# Shema.net
KiCad netlist of a schematic drawn in Altium Designer
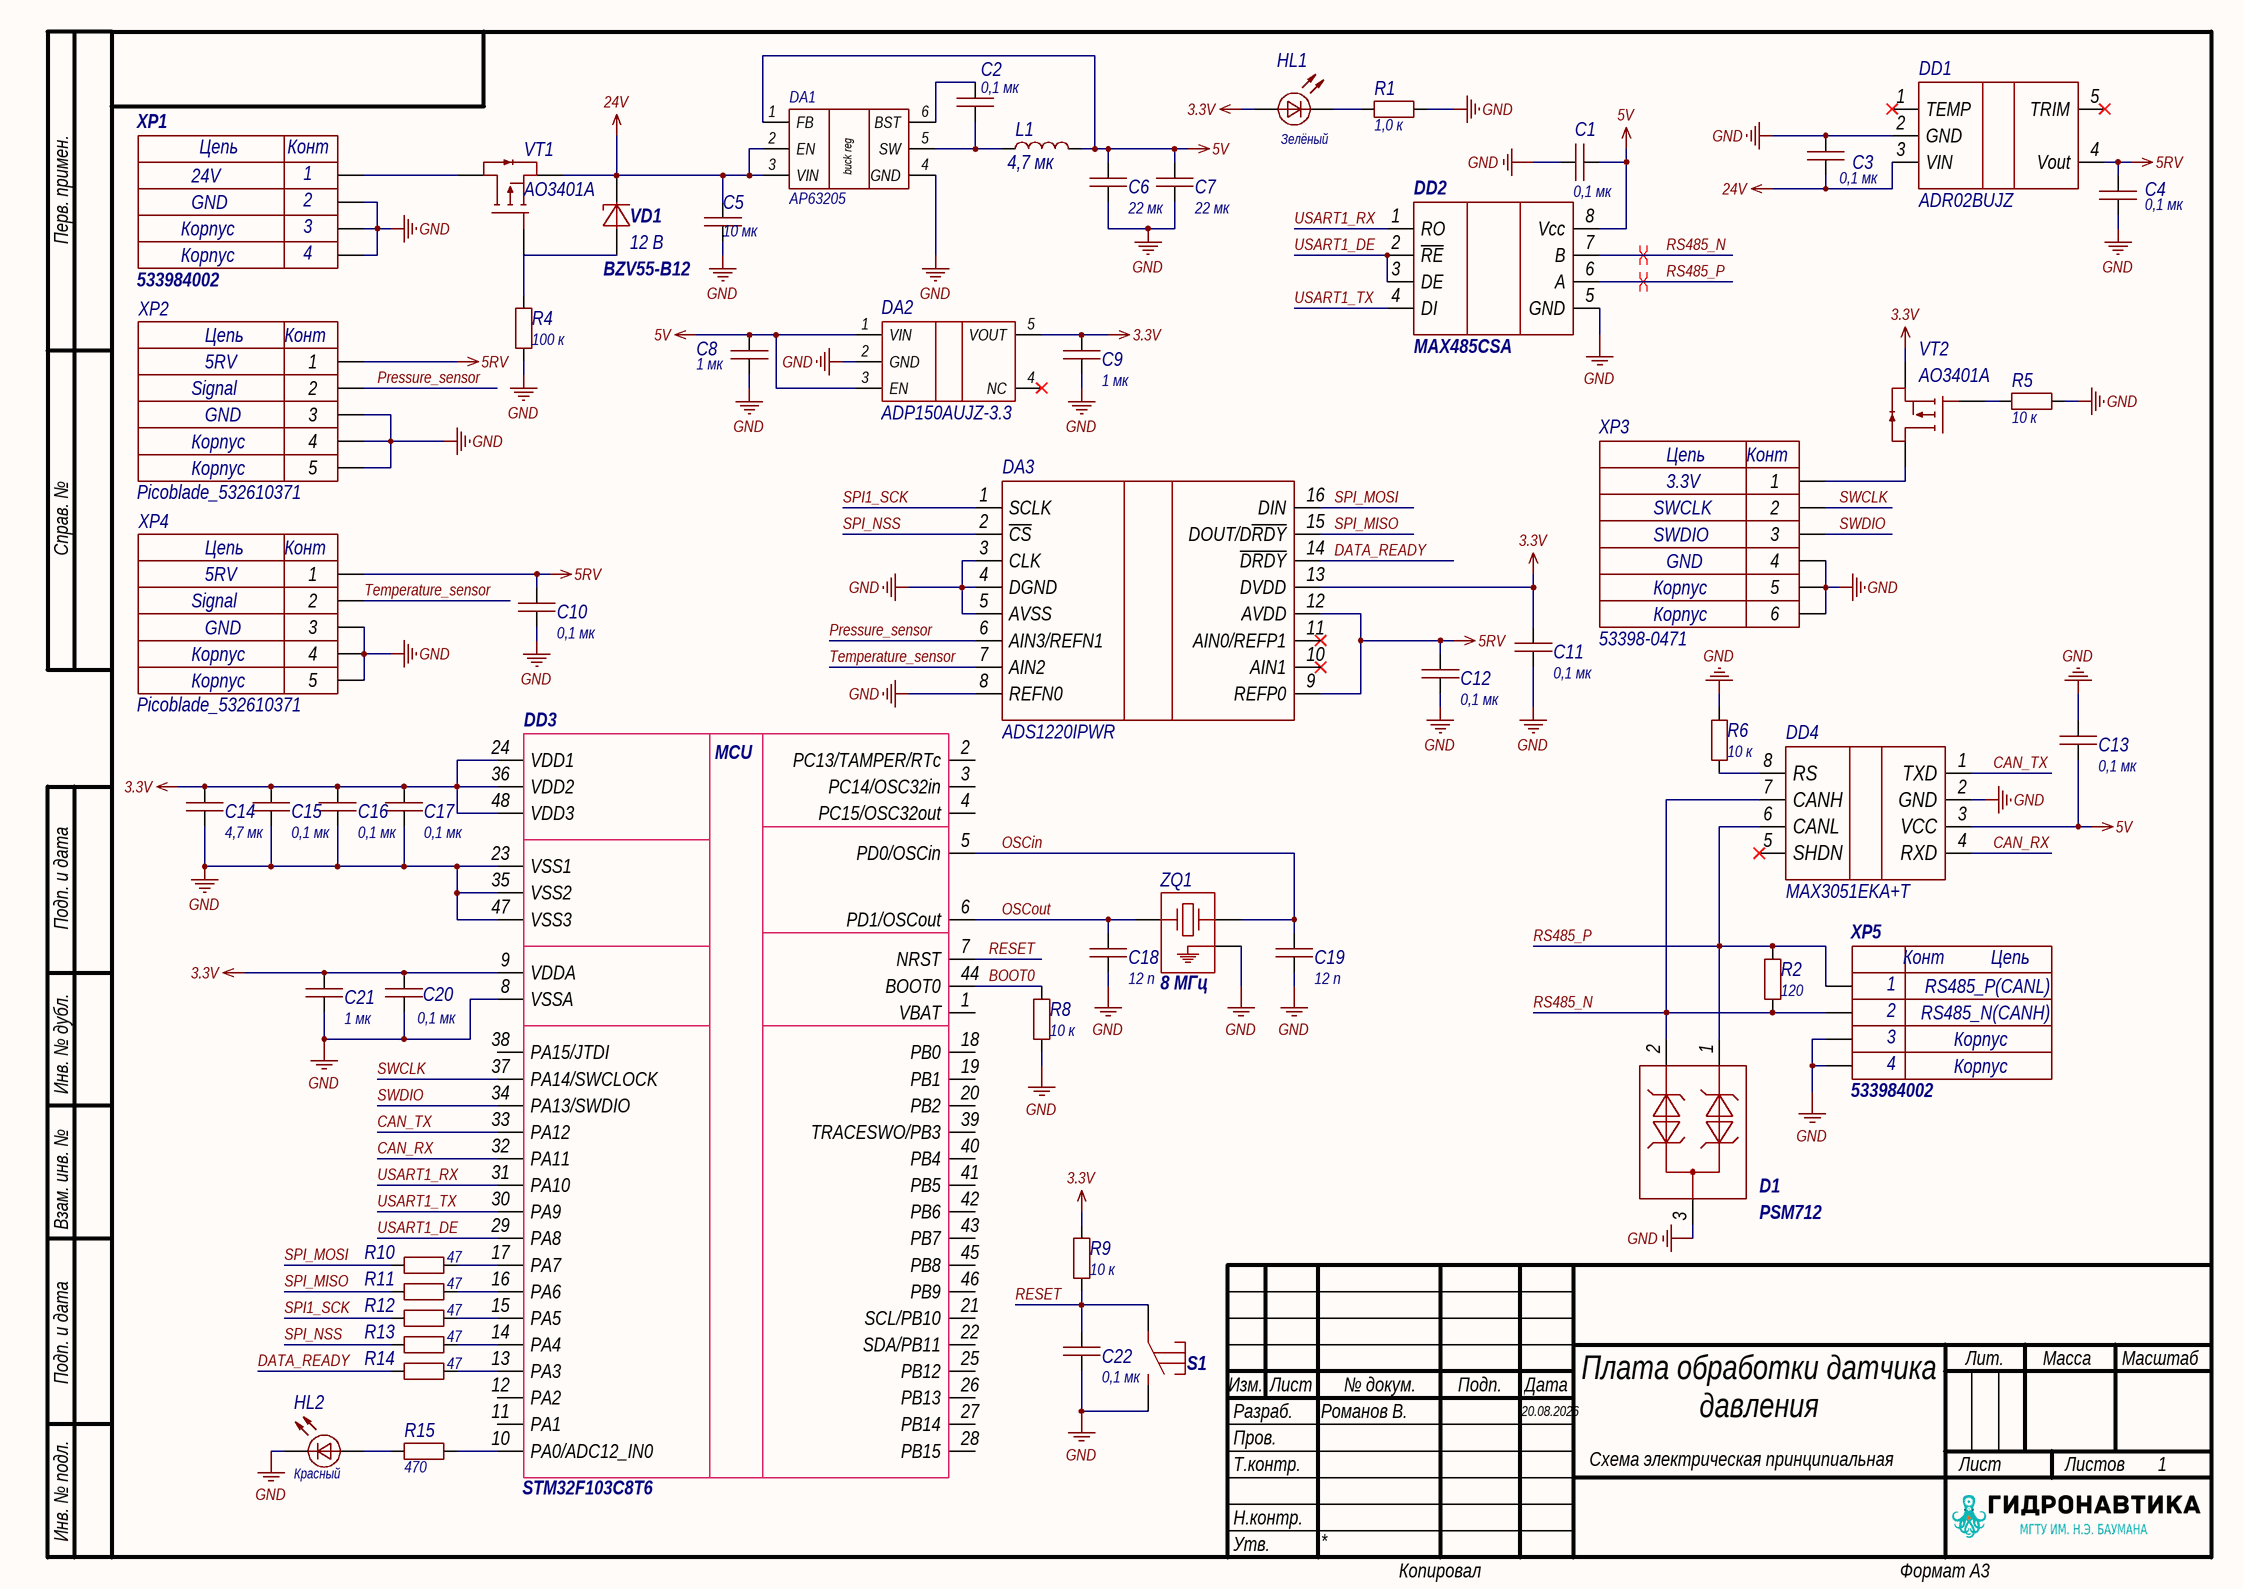
[diagram p0: Shema.SchDoc]

(export (version "E")
  (design (tool "Eeschema 10.0.6"))
  (components
    (comp (ref "C1")
      (value "0,1 мк")
      (footprint "0603C")
      (description "Конденсатор 0603C ёмкостью 0,1 мк 10%, 50 В, X7R")
      (fields (field (name "PART NUMBER") "Capacitor_0,1u_10_50V_X7R_0603C") (field (name "TOLERANCE") "10%"))
      (libsource (lib "Hydrolib") (part "Capacitor"))
    )
    (comp (ref "C2")
      (value "0,1 мк")
      (footprint "0603C")
      (description "Конденсатор 0603C ёмкостью 0,1 мк 10%, 50 В, X7R")
      (fields (field (name "PART NUMBER") "Capacitor_0,1u_10_50V_X7R_0603C") (field (name "TOLERANCE") "10%"))
      (libsource (lib "Hydrolib") (part "Capacitor"))
    )
    (comp (ref "C3")
      (value "0,1 мк")
      (footprint "0603C")
      (description "Конденсатор 0603C ёмкостью 0,1 мк 10%, 50 В, X7R")
      (fields (field (name "PART NUMBER") "Capacitor_0,1u_10_50V_X7R_0603C") (field (name "TOLERANCE") "10%"))
      (libsource (lib "Hydrolib") (part "Capacitor"))
    )
    (comp (ref "C4")
      (value "0,1 мк")
      (footprint "0603C")
      (description "Конденсатор 0603C ёмкостью 0,1 мк 10%, 50 В, X7R")
      (fields (field (name "PART NUMBER") "Capacitor_0,1u_10_50V_X7R_0603C") (field (name "TOLERANCE") "10%"))
      (libsource (lib "Hydrolib") (part "Capacitor"))
    )
    (comp (ref "C5")
      (value "10 мк")
      (footprint "1210C")
      (description "Конденсатор 1210C ёмкостью 10 мк 10%, 35 В, X7R")
      (fields (field (name "PART NUMBER") "Capacitor_10u_10_35V_X7R_1210C") (field (name "TOLERANCE") "10%"))
      (libsource (lib "Hydrolib") (part "Capacitor"))
    )
    (comp (ref "C6")
      (value "22 мк")
      (footprint "1210C")
      (description "Конденсатор 1210C ёмкостью 22 мк 10%, 25 В, X7R")
      (fields (field (name "PART NUMBER") "Capacitor_22u_10_25V_X7R_1210C") (field (name "TOLERANCE") "10%"))
      (libsource (lib "Hydrolib") (part "Capacitor"))
    )
    (comp (ref "C7")
      (value "22 мк")
      (footprint "1210C")
      (description "Конденсатор 1210C ёмкостью 22 мк 10%, 25 В, X7R")
      (fields (field (name "PART NUMBER") "Capacitor_22u_10_25V_X7R_1210C") (field (name "TOLERANCE") "10%"))
      (libsource (lib "Hydrolib") (part "Capacitor"))
    )
    (comp (ref "C8")
      (value "1 мк")
      (footprint "0603C")
      (description "Конденсатор 0603C ёмкостью 1 мк 10%, 25 В, X7R")
      (fields (field (name "PART NUMBER") "Capacitor_1u_10_25V_X7R_0603C") (field (name "TOLERANCE") "10%"))
      (libsource (lib "Hydrolib") (part "Capacitor"))
    )
    (comp (ref "C9")
      (value "1 мк")
      (footprint "0603C")
      (description "Конденсатор 0603C ёмкостью 1 мк 10%, 25 В, X7R")
      (fields (field (name "PART NUMBER") "Capacitor_1u_10_25V_X7R_0603C") (field (name "TOLERANCE") "10%"))
      (libsource (lib "Hydrolib") (part "Capacitor"))
    )
    (comp (ref "C10")
      (value "0,1 мк")
      (footprint "0603C")
      (description "Конденсатор 0603C ёмкостью 0,1 мк 10%, 50 В, X7R")
      (fields (field (name "PART NUMBER") "Capacitor_0,1u_10_50V_X7R_0603C") (field (name "TOLERANCE") "10%"))
      (libsource (lib "Hydrolib") (part "Capacitor"))
    )
    (comp (ref "C11")
      (value "0,1 мк")
      (footprint "0603C")
      (description "Конденсатор 0603C ёмкостью 0,1 мк 10%, 50 В, X7R")
      (fields (field (name "PART NUMBER") "Capacitor_0,1u_10_50V_X7R_0603C") (field (name "TOLERANCE") "10%"))
      (libsource (lib "Hydrolib") (part "Capacitor"))
    )
    (comp (ref "C12")
      (value "0,1 мк")
      (footprint "0603C")
      (description "Конденсатор 0603C ёмкостью 0,1 мк 10%, 50 В, X7R")
      (fields (field (name "PART NUMBER") "Capacitor_0,1u_10_50V_X7R_0603C") (field (name "TOLERANCE") "10%"))
      (libsource (lib "Hydrolib") (part "Capacitor"))
    )
    (comp (ref "C13")
      (value "0,1 мк")
      (footprint "0603C")
      (description "Конденсатор 0603C ёмкостью 0,1 мк 10%, 50 В, X7R")
      (fields (field (name "PART NUMBER") "Capacitor_0,1u_10_50V_X7R_0603C") (field (name "TOLERANCE") "10%"))
      (libsource (lib "Hydrolib") (part "Capacitor"))
    )
    (comp (ref "C14")
      (value "4,7 мк")
      (footprint "1206C")
      (description "Конденсатор 1206C ёмкостью 4,7 мк 10%, 50 В, X7R")
      (fields (field (name "PART NUMBER") "Capacitor_4,7u_10_50V_X7R_1206C") (field (name "TOLERANCE") "10%"))
      (libsource (lib "Hydrolib") (part "Capacitor"))
    )
    (comp (ref "C15")
      (value "0,1 мк")
      (footprint "0603C")
      (description "Конденсатор 0603C ёмкостью 0,1 мк 10%, 50 В, X7R")
      (fields (field (name "PART NUMBER") "Capacitor_0,1u_10_50V_X7R_0603C") (field (name "TOLERANCE") "10%"))
      (libsource (lib "Hydrolib") (part "Capacitor"))
    )
    (comp (ref "C16")
      (value "0,1 мк")
      (footprint "0603C")
      (description "Конденсатор 0603C ёмкостью 0,1 мк 10%, 50 В, X7R")
      (fields (field (name "PART NUMBER") "Capacitor_0,1u_10_50V_X7R_0603C") (field (name "TOLERANCE") "10%"))
      (libsource (lib "Hydrolib") (part "Capacitor"))
    )
    (comp (ref "C17")
      (value "0,1 мк")
      (footprint "0603C")
      (description "Конденсатор 0603C ёмкостью 0,1 мк 10%, 50 В, X7R")
      (fields (field (name "PART NUMBER") "Capacitor_0,1u_10_50V_X7R_0603C") (field (name "TOLERANCE") "10%"))
      (libsource (lib "Hydrolib") (part "Capacitor"))
    )
    (comp (ref "C18")
      (value "12 п")
      (footprint "0603C")
      (description "Конденсатор 0603C ёмкостью 12 п 5%, 50 В, NP0")
      (fields
        (field (name "PART NUMBER") "Capacitor_12p_5_50V_NP0_0603C")
        (field (name "TOLERANCE") "5%")
        (field (name "АВТОР") "glebmih")
      )
      (libsource (lib "Hydrolib") (part "Capacitor"))
    )
    (comp (ref "C19")
      (value "12 п")
      (footprint "0603C")
      (description "Конденсатор 0603C ёмкостью 12 п 5%, 50 В, NP0")
      (fields
        (field (name "PART NUMBER") "Capacitor_12p_5_50V_NP0_0603C")
        (field (name "TOLERANCE") "5%")
        (field (name "АВТОР") "glebmih")
      )
      (libsource (lib "Hydrolib") (part "Capacitor"))
    )
    (comp (ref "C20")
      (value "0,1 мк")
      (footprint "0603C")
      (description "Конденсатор 0603C ёмкостью 0,1 мк 10%, 50 В, X7R")
      (fields (field (name "PART NUMBER") "Capacitor_0,1u_10_50V_X7R_0603C") (field (name "TOLERANCE") "10%"))
      (libsource (lib "Hydrolib") (part "Capacitor"))
    )
    (comp (ref "C21")
      (value "1 мк")
      (footprint "0603C")
      (description "Конденсатор 0603C ёмкостью 1 мк 10%, 25 В, X7R")
      (fields (field (name "PART NUMBER") "Capacitor_1u_10_25V_X7R_0603C") (field (name "TOLERANCE") "10%"))
      (libsource (lib "Hydrolib") (part "Capacitor"))
    )
    (comp (ref "C22")
      (value "0,1 мк")
      (footprint "0603C")
      (description "Конденсатор 0603C ёмкостью 0,1 мк 10%, 50 В, X7R")
      (fields (field (name "PART NUMBER") "Capacitor_0,1u_10_50V_X7R_0603C") (field (name "TOLERANCE") "10%"))
      (libsource (lib "Hydrolib") (part "Capacitor"))
    )
    (comp (ref "D1")
      (value "PSM712")
      (footprint "SOT23-3")
      (description "Защитный диод для линии RS-485")
      (libsource (lib "Hydrolib") (part "TVS_2_2dir"))
    )
    (comp (ref "DA1")
      (value "AP63205")
      (footprint "TSOT26")
      (description "DC-DC понижающий преобразователь, Vin: 3.8 - 40 В; 5 В; 2 А")
      (fields (field (name "АВТОР") "glebmih"))
      (libsource (lib "Hydrolib") (part "AP63205"))
    )
    (comp (ref "DA2")
      (value "ADP150AUJZ-3.3")
      (footprint "SOT23-5")
      (description "Стабилизатор напряжения 3.3В 150мА")
      (fields (field (name "АВТОР") "glebmih"))
      (libsource (lib "Hydrolib") (part "ADP150AUJZ-3.3"))
    )
    (comp (ref "DA3")
      (value "ADS1220IPWR")
      (footprint "TSSOP-16")
      (description "24-Бит Sigma-Delta аналого-цифровой преобразователь")
      (fields (field (name "АВТОР") "Vouka06"))
      (libsource (lib "Hydrolib") (part "ADS1220IPWR"))
    )
    (comp (ref "DD1")
      (value "ADR02BUJZ")
      (footprint "SOT23-5")
      (description "Источник опорного напряжения, 5В")
      (fields (field (name "АВТОР") "Vouka05"))
      (libsource (lib "Hydrolib") (part "ADR02BUJZ"))
    )
    (comp (ref "DD2")
      (value "MAX485CSA")
      (footprint "SOIC-8")
      (description "RS-485 приёмопередатчик")
      (libsource (lib "Hydrolib") (part "MAX485CSA"))
    )
    (comp (ref "DD3")
      (value "STM32F103C8T6")
      (footprint "LQFP48")
      (description "Микроконтроллер")
      (fields (field (name "MANUFACTURER") "ST Microelectronics") (field (name "VALUE1") "MCU"))
      (libsource (lib "Hydrolib") (part "STM32F103C8T6"))
    )
    (comp (ref "DD4")
      (value "MAX3051EKA+T")
      (footprint "SOT-23-8")
      (description "CAN трансивер 1Mbps +3.3В")
      (fields (field (name "АВТОР") "Vouka06"))
      (libsource (lib "Hydrolib") (part "MAX3051EKA+T"))
    )
    (comp (ref "HL1")
      (value "Зелёный")
      (footprint "0805D")
      (description "Светодиод")
      (fields (field (name "PART NUMBER") "LED"))
      (libsource (lib "Hydrolib") (part "LED"))
    )
    (comp (ref "HL2")
      (value "Красный")
      (footprint "0805D")
      (description "Светодиод")
      (fields (field (name "PART NUMBER") "LED"))
      (libsource (lib "Hydrolib") (part "LED"))
    )
    (comp (ref "L1")
      (value "4,7 мк")
      (footprint "IHLP-2525")
      (description "ЧИП-индуктивность экранированная 4,7мкГн ±20% 5,5A 40мОм 2525")
      (fields (field (name "PART NUMBER") "IHLP2525CZER4R7M01"))
      (libsource (lib "Hydrolib") (part "Inductance"))
    )
    (comp (ref "R1")
      (value "1,0 к")
      (footprint "0603R")
      (description "Резистор номиналом 1,0 кОм 1%")
      (fields (field (name "PART NUMBER") "Resistor_1.0k_1_0603") (field (name "TOLERANCE") "1%"))
      (libsource (lib "Hydrolib") (part "Resistor"))
    )
    (comp (ref "R2")
      (value "120")
      (footprint "1206R")
      (description "Резистор номиналом 120 Ом 1%")
      (fields
        (field (name "PART NUMBER") "Resistor_120_1_1206")
        (field (name "TOLERANCE") "1%")
        (field (name "АВТОР") "glebmih")
      )
      (libsource (lib "") (part "Resistor_1"))
    )
    (comp (ref "R4")
      (value "100 к")
      (footprint "0603R")
      (description "Резистор номиналом 100 кОм 1%")
      (fields (field (name "PART NUMBER") "Resistor_100k_1_0603") (field (name "TOLERANCE") "1%"))
      (libsource (lib "") (part "Resistor_1"))
    )
    (comp (ref "R5")
      (value "10 к")
      (footprint "0603R")
      (description "Резистор номиналом 10 кОм 1%")
      (fields (field (name "PART NUMBER") "Resistor_10k_1_0603") (field (name "TOLERANCE") "1%"))
      (libsource (lib "Hydrolib") (part "Resistor"))
    )
    (comp (ref "R6")
      (value "10 к")
      (footprint "0603R")
      (description "Резистор номиналом 10 кОм 1%")
      (fields (field (name "PART NUMBER") "Resistor_10k_1_0603") (field (name "TOLERANCE") "1%"))
      (libsource (lib "Hydrolib") (part "Resistor"))
    )
    (comp (ref "R8")
      (value "10 к")
      (footprint "0603R")
      (description "Резистор номиналом 10 кОм 1%")
      (fields (field (name "PART NUMBER") "Resistor_10k_1_0603") (field (name "TOLERANCE") "1%"))
      (libsource (lib "") (part "Resistor_2"))
    )
    (comp (ref "R9")
      (value "10 к")
      (footprint "0603R")
      (description "Резистор номиналом 10 кОм 1%")
      (fields (field (name "PART NUMBER") "Resistor_10k_1_0603") (field (name "TOLERANCE") "1%"))
      (libsource (lib "") (part "Resistor_2"))
    )
    (comp (ref "R10")
      (value "47")
      (footprint "0603R")
      (description "Резистор номиналом 47 Ом 1%")
      (fields (field (name "PART NUMBER") "Resistor_47_1_0603") (field (name "TOLERANCE") "1%"))
      (libsource (lib "Hydrolib") (part "Resistor"))
    )
    (comp (ref "R11")
      (value "47")
      (footprint "0603R")
      (description "Резистор номиналом 47 Ом 1%")
      (fields (field (name "PART NUMBER") "Resistor_47_1_0603") (field (name "TOLERANCE") "1%"))
      (libsource (lib "Hydrolib") (part "Resistor"))
    )
    (comp (ref "R12")
      (value "47")
      (footprint "0603R")
      (description "Резистор номиналом 47 Ом 1%")
      (fields (field (name "PART NUMBER") "Resistor_47_1_0603") (field (name "TOLERANCE") "1%"))
      (libsource (lib "Hydrolib") (part "Resistor"))
    )
    (comp (ref "R13")
      (value "47")
      (footprint "0603R")
      (description "Резистор номиналом 47 Ом 1%")
      (fields (field (name "PART NUMBER") "Resistor_47_1_0603") (field (name "TOLERANCE") "1%"))
      (libsource (lib "Hydrolib") (part "Resistor"))
    )
    (comp (ref "R14")
      (value "47")
      (footprint "0603R")
      (description "Резистор номиналом 47 Ом 1%")
      (fields (field (name "PART NUMBER") "Resistor_47_1_0603") (field (name "TOLERANCE") "1%"))
      (libsource (lib "Hydrolib") (part "Resistor"))
    )
    (comp (ref "R15")
      (value "470")
      (footprint "0603R")
      (description "Резистор номиналом 470 Ом 1%")
      (fields (field (name "PART NUMBER") "Resistor_470_1_0603") (field (name "TOLERANCE") "1%"))
      (libsource (lib "Hydrolib") (part "Resistor"))
    )
    (comp (ref "S1")
      (value "Tact_button")
      (footprint "Button_SMD_10mm")
      (description "Тактовая кнопка")
      (libsource (lib "Hydrolib") (part "Tact_button"))
    )
    (comp (ref "VD1")
      (value "BZV55-B12")
      (footprint "mini_MELF_3.5mm")
      (description "Стабилитрон 12В, 5%, 0.5Вт")
      (fields (field (name "ALTIUM_VALUE") "12 В") (field (name "АВТОР") "rreali"))
      (libsource (lib "Hydrolib") (part "Zener"))
    )
    (comp (ref "VT1")
      (value "AO3401A")
      (footprint "SOT23-3")
      (description "P-канальный MOSFET")
      (libsource (lib "Hydrolib") (part "MOSFET P-channel 2"))
    )
    (comp (ref "VT2")
      (value "AO3401A")
      (footprint "SOT23-3")
      (description "P-канальный MOSFET")
      (libsource (lib "Hydrolib") (part "MOSFET P-channel 2"))
    )
    (comp (ref "XP1")
      (value "533984002")
      (footprint "Picoblade_533984002")
      (description "2pin, 1.25mm, вилка, PicoBlade, на плату, SMT")
      (fields
        (field (name "VALUE3") "Корпус")
        (field (name "VALUE2") "GND")
        (field (name "VALUE4") "Корпус")
        (field (name "VALUE1") "24V")
        (field (name "PART NUMBER") "Picoblade_533984002")
        (field (name "АВТОР") "rreali")
      )
      (libsource (lib "Hydrolib") (part "Conn_2pin_2shield"))
    )
    (comp (ref "XP2")
      (value "Picoblade_532610371")
      (footprint "CONN_532610001-SD_03_MOL")
      (description "Picoblade 3-pin разъем")
      (fields
        (field (name "VALUE5") "Корпус")
        (field (name "VALUE4") "Корпус")
        (field (name "VALUE3") "GND")
        (field (name "VALUE2") "Signal")
        (field (name "VALUE1") "5RV")
        (field (name "АВТОР") "Vouka06")
      )
      (libsource (lib "Hydrolib") (part "Picoblade_532610371"))
    )
    (comp (ref "XP3")
      (value "53398-0471")
      (footprint "53398-0471")
      (description "Разъем PicoBlade 1.25 мм, 4pin")
      (fields
        (field (name "VALUE6") "Корпус")
        (field (name "VALUE5") "Корпус")
        (field (name "VALUE4") "GND")
        (field (name "VALUE3") "SWDIO")
        (field (name "VALUE2") "SWCLK")
        (field (name "VALUE1") "3.3V")
        (field (name "PART NUMBER") "PicoBlade_53398-0471")
        (field (name "АВТОР") "Vouka06")
      )
      (libsource (lib "Hydrolib") (part "PicoBlade_53398-0471"))
    )
    (comp (ref "XP4")
      (value "Picoblade_532610371")
      (footprint "CONN_532610001-SD_03_MOL")
      (description "Picoblade 3-pin разъем")
      (fields
        (field (name "VALUE5") "Корпус")
        (field (name "VALUE4") "Корпус")
        (field (name "VALUE3") "GND")
        (field (name "VALUE2") "Signal")
        (field (name "VALUE1") "5RV")
        (field (name "АВТОР") "Vouka06")
      )
      (libsource (lib "Hydrolib") (part "Picoblade_532610371"))
    )
    (comp (ref "XP5")
      (value "533984002")
      (footprint "Picoblade_533984002")
      (description "2pin, 1.25mm, вилка, PicoBlade, на плату, SMT")
      (fields
        (field (name "VALUE3") "Корпус")
        (field (name "VALUE2") "RS485_N(CANH)")
        (field (name "VALUE4") "Корпус")
        (field (name "VALUE1") "RS485_P(CANL)")
        (field (name "PART NUMBER") "Picoblade_533984002")
        (field (name "АВТОР") "rreali")
      )
      (libsource (lib "Hydrolib") (part "Conn_2pin_2shield"))
    )
    (comp (ref "ZQ1")
      (value "8 МГц")
      (footprint "QSMD3.2x2.5")
      (description "Кварцевый резонатор с входом земли")
      (fields (field (name "PART NUMBER") "XTAL_GND"))
      (libsource (lib "Hydrolib") (part "XTAL_GND"))
    )
  )
  (nets
    (net (code "1") (name "/BOOT0") (class "Default")
      (node (ref "DD3") (pin "44") (pinfunction "BOOT0_44") (pintype "passive"))
      (node (ref "R8") (pin "1") (pinfunction "1_1") (pintype "passive"))
    )
    (net (code "2") (name "/CAN_RX") (class "Default")
      (node (ref "DD3") (pin "32") (pinfunction "PA11_32") (pintype "passive"))
      (node (ref "DD4") (pin "4") (pinfunction "RXD_4") (pintype "passive"))
    )
    (net (code "3") (name "/CAN_TX") (class "Default")
      (node (ref "DD3") (pin "33") (pinfunction "PA12_33") (pintype "passive"))
      (node (ref "DD4") (pin "1") (pinfunction "TXD_1") (pintype "passive"))
    )
    (net (code "4") (name "/DATA_READY") (class "Default")
      (node (ref "DA3") (pin "14") (pinfunction "~{DRDY}_14") (pintype "passive"))
      (node (ref "R14") (pin "1") (pinfunction "1_1") (pintype "passive"))
    )
    (net (code "5") (name "/OSCin") (class "Default")
      (node (ref "C19") (pin "2") (pinfunction "2_2") (pintype "passive"))
      (node (ref "DD3") (pin "5") (pinfunction "PD0/OSCin_5") (pintype "passive"))
      (node (ref "ZQ1") (pin "2") (pinfunction "2_2") (pintype "passive"))
    )
    (net (code "6") (name "/OSCout") (class "Default")
      (node (ref "C18") (pin "2") (pinfunction "2_2") (pintype "passive"))
      (node (ref "DD3") (pin "6") (pinfunction "PD1/OSCout_6") (pintype "passive"))
      (node (ref "ZQ1") (pin "1") (pinfunction "1_1") (pintype "passive"))
    )
    (net (code "7") (name "/Pressure_sensor") (class "Default")
      (node (ref "DA3") (pin "6") (pinfunction "AIN3/REFN1_6") (pintype "passive"))
      (node (ref "XP2") (pin "2") (pinfunction "2_2") (pintype "passive"))
    )
    (net (code "8") (name "/RESET") (class "Default")
      (node (ref "C22") (pin "1") (pinfunction "1_1") (pintype "passive"))
      (node (ref "DD3") (pin "7") (pinfunction "NRST_7") (pintype "passive"))
      (node (ref "R9") (pin "2") (pinfunction "2_2") (pintype "passive"))
      (node (ref "S1") (pin "1") (pinfunction "1_1") (pintype "passive"))
    )
    (net (code "9") (name "/RS485_N") (class "Default")
      (node (ref "D1") (pin "2") (pinfunction "15_2") (pintype "passive"))
      (node (ref "DD2") (pin "7") (pinfunction "B_7") (pintype "passive"))
      (node (ref "DD4") (pin "7") (pinfunction "CANH_7") (pintype "passive"))
      (node (ref "R2") (pin "1") (pinfunction "1_1") (pintype "passive"))
      (node (ref "XP5") (pin "2") (pinfunction "2_2") (pintype "passive"))
    )
    (net (code "10") (name "/RS485_P") (class "Default")
      (node (ref "D1") (pin "1") (pinfunction "14_1") (pintype "passive"))
      (node (ref "DD2") (pin "6") (pinfunction "A_6") (pintype "passive"))
      (node (ref "DD4") (pin "6") (pinfunction "CANL_6") (pintype "passive"))
      (node (ref "R2") (pin "2") (pinfunction "2_2") (pintype "passive"))
      (node (ref "XP5") (pin "1") (pinfunction "1_1") (pintype "passive"))
    )
    (net (code "11") (name "/SPI1_SCK") (class "Default")
      (node (ref "DA3") (pin "1") (pinfunction "SCLK_1") (pintype "passive"))
      (node (ref "R12") (pin "1") (pinfunction "1_1") (pintype "passive"))
    )
    (net (code "12") (name "/SPI_MISO") (class "Default")
      (node (ref "DA3") (pin "15") (pinfunction "DOUT/D~{RDY}_15") (pintype "passive"))
      (node (ref "R11") (pin "1") (pinfunction "1_1") (pintype "passive"))
    )
    (net (code "13") (name "/SPI_MOSI") (class "Default")
      (node (ref "DA3") (pin "16") (pinfunction "DIN_16") (pintype "passive"))
      (node (ref "R10") (pin "1") (pinfunction "1_1") (pintype "passive"))
    )
    (net (code "14") (name "/SPI_NSS") (class "Default")
      (node (ref "DA3") (pin "2") (pinfunction "~{CS}_2") (pintype "passive"))
      (node (ref "R13") (pin "1") (pinfunction "1_1") (pintype "passive"))
    )
    (net (code "15") (name "/SWCLK") (class "Default")
      (node (ref "DD3") (pin "37") (pinfunction "PA14/SWCLOCK_37") (pintype "passive"))
      (node (ref "XP3") (pin "2") (pinfunction "2_2") (pintype "passive"))
    )
    (net (code "16") (name "/SWDIO") (class "Default")
      (node (ref "DD3") (pin "34") (pinfunction "PA13/SWDIO_34") (pintype "passive"))
      (node (ref "XP3") (pin "3") (pinfunction "3_3") (pintype "passive"))
    )
    (net (code "17") (name "/Temperature_sensor") (class "Default")
      (node (ref "DA3") (pin "7") (pinfunction "AIN2_7") (pintype "passive"))
      (node (ref "XP4") (pin "2") (pinfunction "2_2") (pintype "passive"))
    )
    (net (code "18") (name "/USART1_DE") (class "Default")
      (node (ref "DD2") (pin "2") (pinfunction "RE_2") (pintype "passive"))
      (node (ref "DD2") (pin "3") (pinfunction "DE_3") (pintype "passive"))
      (node (ref "DD3") (pin "29") (pinfunction "PA8_29") (pintype "passive"))
    )
    (net (code "19") (name "/USART1_RX") (class "Default")
      (node (ref "DD2") (pin "1") (pinfunction "RO_1") (pintype "passive"))
      (node (ref "DD3") (pin "31") (pinfunction "PA10_31") (pintype "passive"))
    )
    (net (code "20") (name "/USART1_TX") (class "Default")
      (node (ref "DD2") (pin "4") (pinfunction "DI_4") (pintype "passive"))
      (node (ref "DD3") (pin "30") (pinfunction "PA9_30") (pintype "passive"))
    )
    (net (code "21") (name "3.3V") (class "Default")
      (node (ref "C11") (pin "2") (pinfunction "2_2") (pintype "passive"))
      (node (ref "C14") (pin "2") (pinfunction "2_2") (pintype "passive"))
      (node (ref "C15") (pin "2") (pinfunction "2_2") (pintype "passive"))
      (node (ref "C16") (pin "2") (pinfunction "2_2") (pintype "passive"))
      (node (ref "C17") (pin "2") (pinfunction "2_2") (pintype "passive"))
      (node (ref "C20") (pin "2") (pinfunction "2_2") (pintype "passive"))
      (node (ref "C21") (pin "2") (pinfunction "2_2") (pintype "passive"))
      (node (ref "C9") (pin "2") (pinfunction "2_2") (pintype "passive"))
      (node (ref "DA2") (pin "5") (pinfunction "VOUT_5") (pintype "passive"))
      (node (ref "DA3") (pin "13") (pinfunction "DVDD_13") (pintype "passive"))
      (node (ref "DD3") (pin "24") (pinfunction "VDD1_24") (pintype "passive"))
      (node (ref "DD3") (pin "36") (pinfunction "VDD2_36") (pintype "passive"))
      (node (ref "DD3") (pin "48") (pinfunction "VDD3_48") (pintype "passive"))
      (node (ref "DD3") (pin "9") (pinfunction "VDDA_9") (pintype "passive"))
      (node (ref "HL1") (pin "1") (pinfunction "1_1") (pintype "passive"))
      (node (ref "R9") (pin "1") (pinfunction "1_1") (pintype "passive"))
      (node (ref "VT2") (pin "2") (pinfunction "2_2") (pintype "passive"))
    )
    (net (code "22") (name "5RV") (class "Default")
      (node (ref "C10") (pin "2") (pinfunction "2_2") (pintype "passive"))
      (node (ref "C12") (pin "2") (pinfunction "2_2") (pintype "passive"))
      (node (ref "C4") (pin "2") (pinfunction "2_2") (pintype "passive"))
      (node (ref "DA3") (pin "12") (pinfunction "AVDD_12") (pintype "passive"))
      (node (ref "DA3") (pin "9") (pinfunction "REFP0_9") (pintype "passive"))
      (node (ref "DD1") (pin "4") (pinfunction "Vout_4") (pintype "passive"))
      (node (ref "XP2") (pin "1") (pinfunction "1_1") (pintype "passive"))
      (node (ref "XP4") (pin "1") (pinfunction "1_1") (pintype "passive"))
    )
    (net (code "23") (name "5V") (class "Default")
      (node (ref "C1") (pin "2") (pinfunction "2_2") (pintype "passive"))
      (node (ref "C13") (pin "2") (pinfunction "2_2") (pintype "passive"))
      (node (ref "C6") (pin "2") (pinfunction "2_2") (pintype "passive"))
      (node (ref "C7") (pin "2") (pinfunction "2_2") (pintype "passive"))
      (node (ref "C8") (pin "2") (pinfunction "2_2") (pintype "passive"))
      (node (ref "DA1") (pin "1") (pinfunction "FB_1") (pintype "passive"))
      (node (ref "DA2") (pin "1") (pinfunction "VIN_1") (pintype "passive"))
      (node (ref "DA2") (pin "3") (pinfunction "EN_3") (pintype "passive"))
      (node (ref "DD2") (pin "8") (pinfunction "Vcc_8") (pintype "passive"))
      (node (ref "DD4") (pin "3") (pinfunction "VCC_3") (pintype "passive"))
      (node (ref "L1") (pin "2") (pinfunction "2_2") (pintype "passive"))
    )
    (net (code "24") (name "24V") (class "Default")
      (node (ref "C3") (pin "1") (pinfunction "1_1") (pintype "passive"))
      (node (ref "C5") (pin "2") (pinfunction "2_2") (pintype "passive"))
      (node (ref "DA1") (pin "2") (pinfunction "EN_2") (pintype "passive"))
      (node (ref "DA1") (pin "3") (pinfunction "VIN_3") (pintype "passive"))
      (node (ref "DD1") (pin "3") (pinfunction "VIN_3") (pintype "passive"))
      (node (ref "VD1") (pin "2") (pinfunction "2_2") (pintype "passive"))
      (node (ref "VT1") (pin "2") (pinfunction "2_2") (pintype "passive"))
    )
    (net (code "25") (name "GND") (class "Default")
      (node (ref "C1") (pin "1") (pinfunction "1_1") (pintype "passive"))
      (node (ref "C10") (pin "1") (pinfunction "1_1") (pintype "passive"))
      (node (ref "C11") (pin "1") (pinfunction "1_1") (pintype "passive"))
      (node (ref "C12") (pin "1") (pinfunction "1_1") (pintype "passive"))
      (node (ref "C13") (pin "1") (pinfunction "1_1") (pintype "passive"))
      (node (ref "C14") (pin "1") (pinfunction "1_1") (pintype "passive"))
      (node (ref "C15") (pin "1") (pinfunction "1_1") (pintype "passive"))
      (node (ref "C16") (pin "1") (pinfunction "1_1") (pintype "passive"))
      (node (ref "C17") (pin "1") (pinfunction "1_1") (pintype "passive"))
      (node (ref "C18") (pin "1") (pinfunction "1_1") (pintype "passive"))
      (node (ref "C19") (pin "1") (pinfunction "1_1") (pintype "passive"))
      (node (ref "C20") (pin "1") (pinfunction "1_1") (pintype "passive"))
      (node (ref "C21") (pin "1") (pinfunction "1_1") (pintype "passive"))
      (node (ref "C22") (pin "2") (pinfunction "2_2") (pintype "passive"))
      (node (ref "C3") (pin "2") (pinfunction "2_2") (pintype "passive"))
      (node (ref "C4") (pin "1") (pinfunction "1_1") (pintype "passive"))
      (node (ref "C5") (pin "1") (pinfunction "1_1") (pintype "passive"))
      (node (ref "C6") (pin "1") (pinfunction "1_1") (pintype "passive"))
      (node (ref "C7") (pin "1") (pinfunction "1_1") (pintype "passive"))
      (node (ref "C8") (pin "1") (pinfunction "1_1") (pintype "passive"))
      (node (ref "C9") (pin "1") (pinfunction "1_1") (pintype "passive"))
      (node (ref "D1") (pin "3") (pinfunction "16_3") (pintype "passive"))
      (node (ref "DA1") (pin "4") (pinfunction "GND_4") (pintype "passive"))
      (node (ref "DA2") (pin "2") (pinfunction "GND_2") (pintype "passive"))
      (node (ref "DA3") (pin "3") (pinfunction "CLK_3") (pintype "passive"))
      (node (ref "DA3") (pin "4") (pinfunction "DGND_4") (pintype "passive"))
      (node (ref "DA3") (pin "5") (pinfunction "AVSS_5") (pintype "passive"))
      (node (ref "DA3") (pin "8") (pinfunction "REFN0_8") (pintype "passive"))
      (node (ref "DD1") (pin "2") (pinfunction "GND_2") (pintype "passive"))
      (node (ref "DD2") (pin "5") (pinfunction "GND_5") (pintype "passive"))
      (node (ref "DD3") (pin "23") (pinfunction "VSS1_23") (pintype "passive"))
      (node (ref "DD3") (pin "35") (pinfunction "VSS2_35") (pintype "passive"))
      (node (ref "DD3") (pin "47") (pinfunction "VSS3_47") (pintype "passive"))
      (node (ref "DD3") (pin "8") (pinfunction "VSSA_8") (pintype "passive"))
      (node (ref "DD4") (pin "2") (pinfunction "GND_2") (pintype "passive"))
      (node (ref "HL2") (pin "2") (pinfunction "2_2") (pintype "passive"))
      (node (ref "R1") (pin "2") (pinfunction "2_2") (pintype "passive"))
      (node (ref "R4") (pin "1") (pinfunction "1_1") (pintype "passive"))
      (node (ref "R5") (pin "2") (pinfunction "2_2") (pintype "passive"))
      (node (ref "R6") (pin "2") (pinfunction "2_2") (pintype "passive"))
      (node (ref "R8") (pin "2") (pinfunction "2_2") (pintype "passive"))
      (node (ref "S1") (pin "2") (pinfunction "2_2") (pintype "passive"))
      (node (ref "XP1") (pin "2") (pinfunction "2_2") (pintype "passive"))
      (node (ref "XP1") (pin "3") (pinfunction "3_3") (pintype "passive"))
      (node (ref "XP1") (pin "4") (pinfunction "4_4") (pintype "passive"))
      (node (ref "XP2") (pin "3") (pinfunction "3_3") (pintype "passive"))
      (node (ref "XP2") (pin "4") (pinfunction "4_4") (pintype "passive"))
      (node (ref "XP2") (pin "5") (pinfunction "5_5") (pintype "passive"))
      (node (ref "XP3") (pin "4") (pinfunction "4_4") (pintype "passive"))
      (node (ref "XP3") (pin "5") (pinfunction "5_5") (pintype "passive"))
      (node (ref "XP3") (pin "6") (pinfunction "6_6") (pintype "passive"))
      (node (ref "XP4") (pin "3") (pinfunction "3_3") (pintype "passive"))
      (node (ref "XP4") (pin "4") (pinfunction "4_4") (pintype "passive"))
      (node (ref "XP4") (pin "5") (pinfunction "5_5") (pintype "passive"))
      (node (ref "XP5") (pin "3") (pinfunction "3_3") (pintype "passive"))
      (node (ref "XP5") (pin "4") (pinfunction "4_4") (pintype "passive"))
      (node (ref "ZQ1") (pin "3") (pinfunction "3_3") (pintype "passive"))
    )
    (net (code "26") (name "Net-(DA1-BST)") (class "Default")
      (node (ref "C2") (pin "2") (pinfunction "2_2") (pintype "passive"))
      (node (ref "DA1") (pin "6") (pinfunction "BST_6") (pintype "passive"))
    )
    (net (code "27") (name "Net-(DA1-SW)") (class "Default")
      (node (ref "C2") (pin "1") (pinfunction "1_1") (pintype "passive"))
      (node (ref "DA1") (pin "5") (pinfunction "SW_5") (pintype "passive"))
      (node (ref "L1") (pin "1") (pinfunction "1_1") (pintype "passive"))
    )
    (net (code "28") (name "Net-(DD3-PA0{slash}ADC12_IN0)") (class "Default")
      (node (ref "DD3") (pin "10") (pinfunction "PA0/ADC12_IN0_10") (pintype "passive"))
      (node (ref "R15") (pin "2") (pinfunction "2_2") (pintype "passive"))
    )
    (net (code "29") (name "Net-(DD3-PA3)") (class "Default")
      (node (ref "DD3") (pin "13") (pinfunction "PA3_13") (pintype "passive"))
      (node (ref "R14") (pin "2") (pinfunction "2_2") (pintype "passive"))
    )
    (net (code "30") (name "Net-(DD3-PA4)") (class "Default")
      (node (ref "DD3") (pin "14") (pinfunction "PA4_14") (pintype "passive"))
      (node (ref "R13") (pin "2") (pinfunction "2_2") (pintype "passive"))
    )
    (net (code "31") (name "Net-(DD3-PA5)") (class "Default")
      (node (ref "DD3") (pin "15") (pinfunction "PA5_15") (pintype "passive"))
      (node (ref "R12") (pin "2") (pinfunction "2_2") (pintype "passive"))
    )
    (net (code "32") (name "Net-(DD3-PA6)") (class "Default")
      (node (ref "DD3") (pin "16") (pinfunction "PA6_16") (pintype "passive"))
      (node (ref "R11") (pin "2") (pinfunction "2_2") (pintype "passive"))
    )
    (net (code "33") (name "Net-(DD3-PA7)") (class "Default")
      (node (ref "DD3") (pin "17") (pinfunction "PA7_17") (pintype "passive"))
      (node (ref "R10") (pin "2") (pinfunction "2_2") (pintype "passive"))
    )
    (net (code "34") (name "Net-(DD4-RS)") (class "Default")
      (node (ref "DD4") (pin "8") (pinfunction "RS_8") (pintype "passive"))
      (node (ref "R6") (pin "1") (pinfunction "1_1") (pintype "passive"))
    )
    (net (code "35") (name "Net-(HL1-Pad2)") (class "Default")
      (node (ref "HL1") (pin "2") (pinfunction "2_2") (pintype "passive"))
      (node (ref "R1") (pin "1") (pinfunction "1_1") (pintype "passive"))
    )
    (net (code "36") (name "Net-(HL2-Pad1)") (class "Default")
      (node (ref "HL2") (pin "1") (pinfunction "1_1") (pintype "passive"))
      (node (ref "R15") (pin "1") (pinfunction "1_1") (pintype "passive"))
    )
    (net (code "37") (name "Net-(R4-Pad2)") (class "Default")
      (node (ref "R4") (pin "2") (pinfunction "2_2") (pintype "passive"))
      (node (ref "VD1") (pin "1") (pinfunction "1_1") (pintype "passive"))
      (node (ref "VT1") (pin "1") (pinfunction "1_1") (pintype "passive"))
    )
    (net (code "38") (name "Net-(R5-Pad1)") (class "Default")
      (node (ref "R5") (pin "1") (pinfunction "1_1") (pintype "passive"))
      (node (ref "VT2") (pin "1") (pinfunction "1_1") (pintype "passive"))
    )
    (net (code "39") (name "Net-(VT1-Pad3)") (class "Default")
      (node (ref "VT1") (pin "3") (pinfunction "3_3") (pintype "passive"))
      (node (ref "XP1") (pin "1") (pinfunction "1_1") (pintype "passive"))
    )
    (net (code "40") (name "Net-(VT2-Pad3)") (class "Default")
      (node (ref "VT2") (pin "3") (pinfunction "3_3") (pintype "passive"))
      (node (ref "XP3") (pin "1") (pinfunction "1_1") (pintype "passive"))
    )
    (net (code "41") (name "unconnected-(DA2-NC-Pad4)") (class "Default")
      (node (ref "DA2") (pin "4") (pinfunction "NC_4") (pintype "passive+no_connect"))
    )
    (net (code "42") (name "unconnected-(DA3-AIN0{slash}REFP1-Pad11)") (class "Default")
      (node (ref "DA3") (pin "11") (pinfunction "AIN0/REFP1_11") (pintype "passive+no_connect"))
    )
    (net (code "43") (name "unconnected-(DA3-AIN1-Pad10)") (class "Default")
      (node (ref "DA3") (pin "10") (pinfunction "AIN1_10") (pintype "passive+no_connect"))
    )
    (net (code "44") (name "unconnected-(DD1-TEMP-Pad1)") (class "Default")
      (node (ref "DD1") (pin "1") (pinfunction "TEMP_1") (pintype "passive+no_connect"))
    )
    (net (code "45") (name "unconnected-(DD1-TRIM-Pad5)") (class "Default")
      (node (ref "DD1") (pin "5") (pinfunction "TRIM_5") (pintype "passive+no_connect"))
    )
    (net (code "46") (name "unconnected-(DD3-PA1-Pad11)") (class "Default")
      (node (ref "DD3") (pin "11") (pinfunction "PA1_11") (pintype "passive"))
    )
    (net (code "47") (name "unconnected-(DD3-PA2-Pad12)") (class "Default")
      (node (ref "DD3") (pin "12") (pinfunction "PA2_12") (pintype "passive"))
    )
    (net (code "48") (name "unconnected-(DD3-PA15{slash}JTDI-Pad38)") (class "Default")
      (node (ref "DD3") (pin "38") (pinfunction "PA15/JTDI_38") (pintype "passive"))
    )
    (net (code "49") (name "unconnected-(DD3-PB0-Pad18)") (class "Default")
      (node (ref "DD3") (pin "18") (pinfunction "PB0_18") (pintype "passive"))
    )
    (net (code "50") (name "unconnected-(DD3-PB1-Pad19)") (class "Default")
      (node (ref "DD3") (pin "19") (pinfunction "PB1_19") (pintype "passive"))
    )
    (net (code "51") (name "unconnected-(DD3-PB2-Pad20)") (class "Default")
      (node (ref "DD3") (pin "20") (pinfunction "PB2_20") (pintype "passive"))
    )
    (net (code "52") (name "unconnected-(DD3-PB4-Pad40)") (class "Default")
      (node (ref "DD3") (pin "40") (pinfunction "PB4_40") (pintype "passive"))
    )
    (net (code "53") (name "unconnected-(DD3-PB5-Pad41)") (class "Default")
      (node (ref "DD3") (pin "41") (pinfunction "PB5_41") (pintype "passive"))
    )
    (net (code "54") (name "unconnected-(DD3-PB6-Pad42)") (class "Default")
      (node (ref "DD3") (pin "42") (pinfunction "PB6_42") (pintype "passive"))
    )
    (net (code "55") (name "unconnected-(DD3-PB7-Pad43)") (class "Default")
      (node (ref "DD3") (pin "43") (pinfunction "PB7_43") (pintype "passive"))
    )
    (net (code "56") (name "unconnected-(DD3-PB8-Pad45)") (class "Default")
      (node (ref "DD3") (pin "45") (pinfunction "PB8_45") (pintype "passive"))
    )
    (net (code "57") (name "unconnected-(DD3-PB9-Pad46)") (class "Default")
      (node (ref "DD3") (pin "46") (pinfunction "PB9_46") (pintype "passive"))
    )
    (net (code "58") (name "unconnected-(DD3-PB12-Pad25)") (class "Default")
      (node (ref "DD3") (pin "25") (pinfunction "PB12_25") (pintype "passive"))
    )
    (net (code "59") (name "unconnected-(DD3-PB13-Pad26)") (class "Default")
      (node (ref "DD3") (pin "26") (pinfunction "PB13_26") (pintype "passive"))
    )
    (net (code "60") (name "unconnected-(DD3-PB14-Pad27)") (class "Default")
      (node (ref "DD3") (pin "27") (pinfunction "PB14_27") (pintype "passive"))
    )
    (net (code "61") (name "unconnected-(DD3-PB15-Pad28)") (class "Default")
      (node (ref "DD3") (pin "28") (pinfunction "PB15_28") (pintype "passive"))
    )
    (net (code "62") (name "unconnected-(DD3-PC13{slash}TAMPER{slash}RTc-Pad2)") (class "Default")
      (node (ref "DD3") (pin "2") (pinfunction "PC13/TAMPER/RTc_2") (pintype "passive"))
    )
    (net (code "63") (name "unconnected-(DD3-PC14{slash}OSC32in-Pad3)") (class "Default")
      (node (ref "DD3") (pin "3") (pinfunction "PC14/OSC32in_3") (pintype "passive"))
    )
    (net (code "64") (name "unconnected-(DD3-PC15{slash}OSC32out-Pad4)") (class "Default")
      (node (ref "DD3") (pin "4") (pinfunction "PC15/OSC32out_4") (pintype "passive"))
    )
    (net (code "65") (name "unconnected-(DD3-SCL{slash}PB10-Pad21)") (class "Default")
      (node (ref "DD3") (pin "21") (pinfunction "SCL/PB10_21") (pintype "passive"))
    )
    (net (code "66") (name "unconnected-(DD3-SDA{slash}PB11-Pad22)") (class "Default")
      (node (ref "DD3") (pin "22") (pinfunction "SDA/PB11_22") (pintype "passive"))
    )
    (net (code "67") (name "unconnected-(DD3-TRACESWO{slash}PB3-Pad39)") (class "Default")
      (node (ref "DD3") (pin "39") (pinfunction "TRACESWO/PB3_39") (pintype "passive"))
    )
    (net (code "68") (name "unconnected-(DD3-VBAT-Pad1)") (class "Default")
      (node (ref "DD3") (pin "1") (pinfunction "VBAT_1") (pintype "passive"))
    )
    (net (code "69") (name "unconnected-(DD4-SHDN-Pad5)") (class "Default")
      (node (ref "DD4") (pin "5") (pinfunction "SHDN_5") (pintype "passive+no_connect"))
    )
  )
)
